# JTAG_Programmer.net
KiCad netlist of a schematic drawn in EAGLE
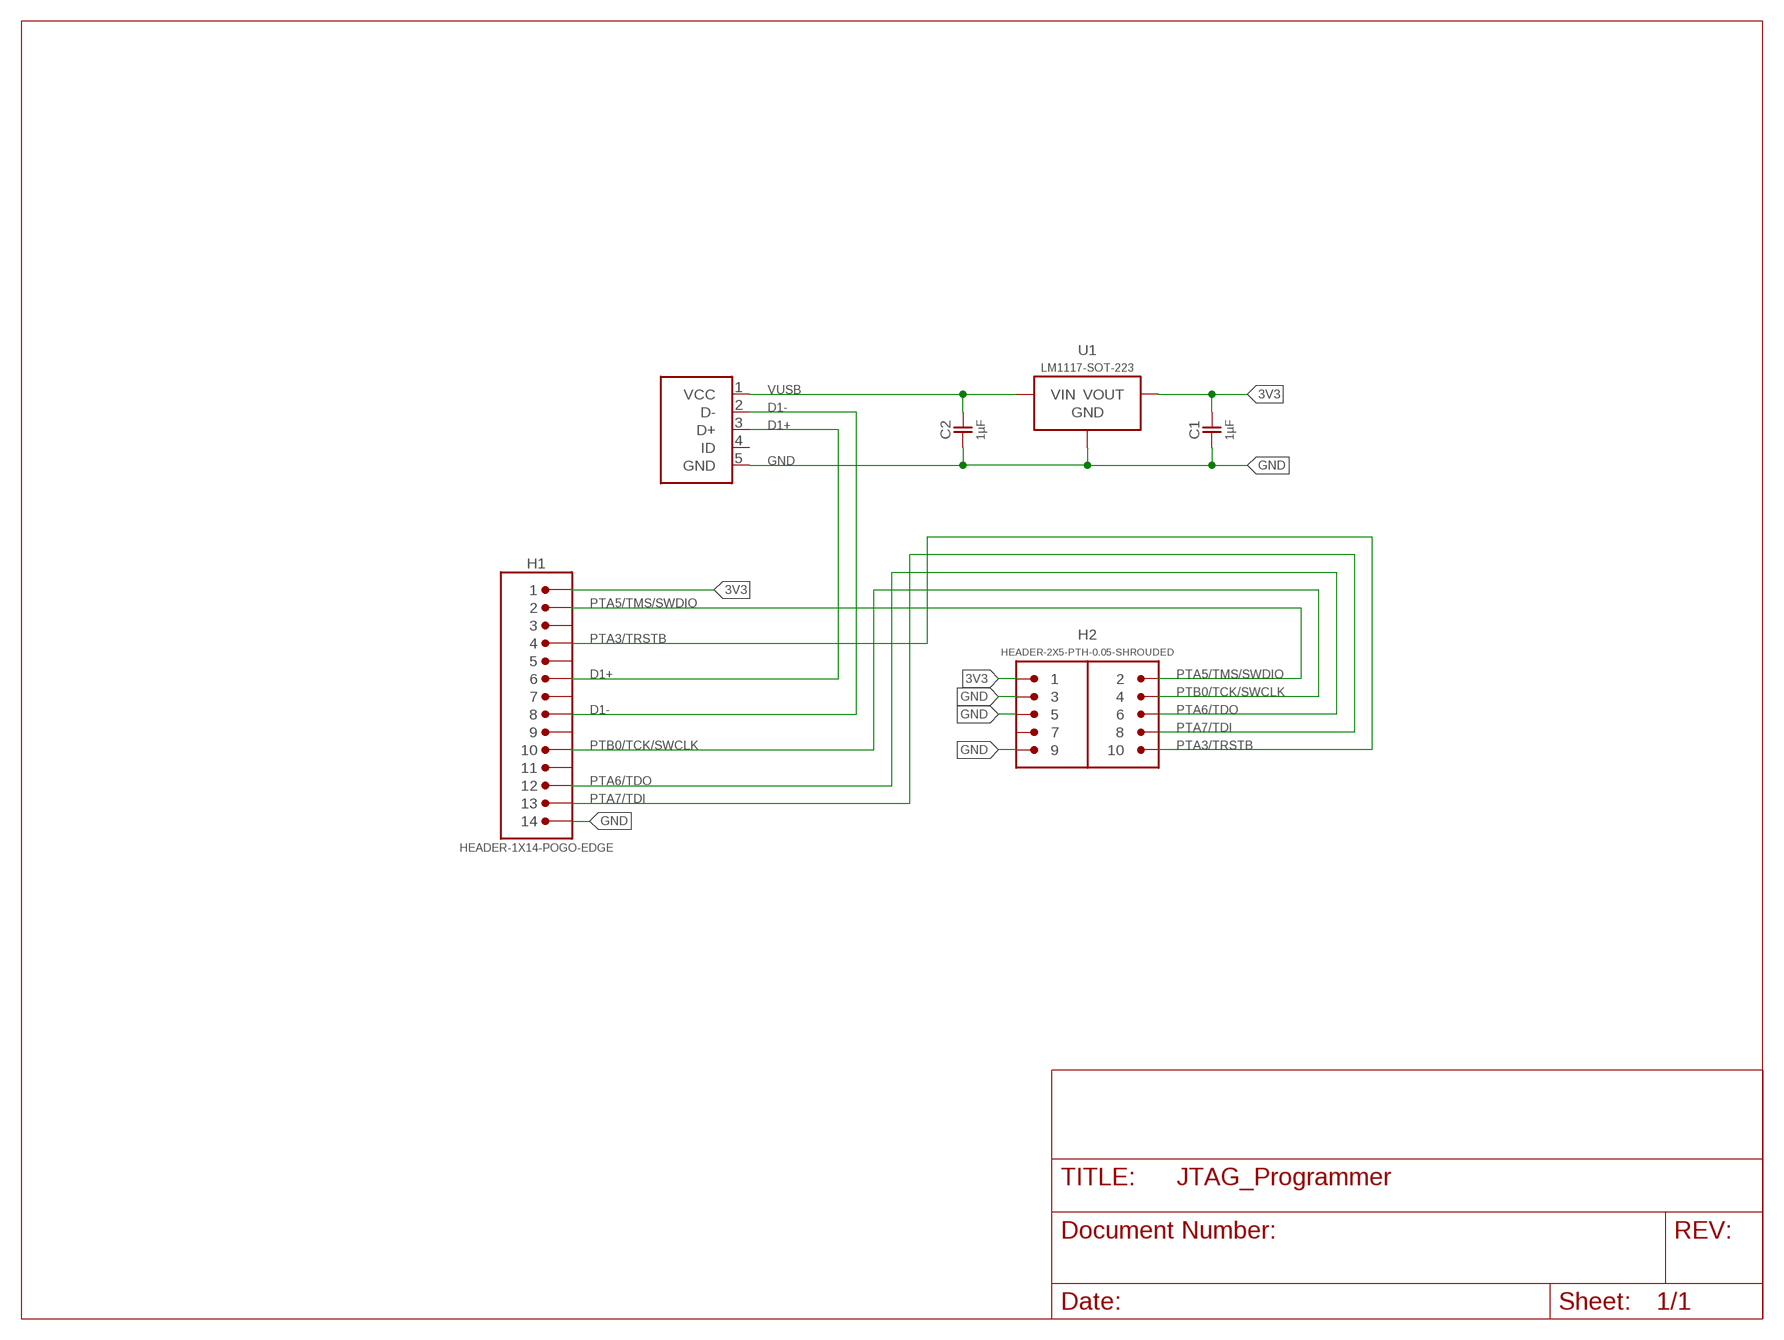
[diagram p0: schematic, sheet 1]

(export (version "E")
  (design (tool "Eeschema 10.0.6"))
  (components
    (comp (ref "C1")
      (value "1µF")
      (footprint "eagle-import:0805-NP")
      (libsource (lib "eagle-import") (part "CAP-NP-0805"))
    )
    (comp (ref "C2")
      (value "1µF")
      (footprint "eagle-import:0805-NP")
      (libsource (lib "eagle-import") (part "CAP-NP-0805"))
    )
    (comp (ref "H1")
      (value "HEADER-1X14-POGO-EDGE")
      (footprint "eagle-import:2X7-1.27MM-POGO-EDGE")
      (libsource (lib "eagle-import") (part "HEADER-1X14-POGO-EDGE"))
    )
    (comp (ref "H2")
      (value "HEADER-2X5-PTH-0.05-SHROUDED")
      (footprint "eagle-import:PTH-0.05-2X5-SHROUDED")
      (libsource (lib "eagle-import") (part "HEADER-2X5-PTH-0.05-SHROUDED"))
    )
    (comp (ref "J1")
      (value "USB-5-MICRO-B")
      (footprint "eagle-import:USB-MICRO-B")
      (libsource (lib "eagle-import") (part "USB-5-MICRO-B"))
    )
    (comp (ref "U1")
      (value "LM1117-SOT-223")
      (footprint "eagle-import:SOT-223")
      (libsource (lib "eagle-import") (part "LM1117-SOT-223"))
    )
  )
  (nets
    (net (code "1") (name "/D1+") (class "Default")
      (node (ref "H1") (pin "6") (pinfunction "6_6") (pintype "bidirectional"))
      (node (ref "J1") (pin "3") (pinfunction "D+_3") (pintype "bidirectional"))
    )
    (net (code "2") (name "/D1-") (class "Default")
      (node (ref "H1") (pin "8") (pinfunction "8_8") (pintype "bidirectional"))
      (node (ref "J1") (pin "2") (pinfunction "D-_2") (pintype "bidirectional"))
    )
    (net (code "3") (name "/PTA3{slash}TRSTB") (class "Default")
      (node (ref "H1") (pin "4") (pinfunction "4_4") (pintype "bidirectional"))
      (node (ref "H2") (pin "10") (pinfunction "10_10") (pintype "bidirectional"))
    )
    (net (code "4") (name "/PTA5{slash}TMS{slash}SWDIO") (class "Default")
      (node (ref "H1") (pin "2") (pinfunction "2_2") (pintype "bidirectional"))
      (node (ref "H2") (pin "2") (pinfunction "2_2") (pintype "bidirectional"))
    )
    (net (code "5") (name "/PTA6{slash}TDO") (class "Default")
      (node (ref "H1") (pin "12") (pinfunction "12_12") (pintype "bidirectional"))
      (node (ref "H2") (pin "6") (pinfunction "6_6") (pintype "bidirectional"))
    )
    (net (code "6") (name "/PTA7{slash}TDI") (class "Default")
      (node (ref "H1") (pin "13") (pinfunction "13_13") (pintype "bidirectional"))
      (node (ref "H2") (pin "8") (pinfunction "8_8") (pintype "bidirectional"))
    )
    (net (code "7") (name "/PTB0{slash}TCK{slash}SWCLK") (class "Default")
      (node (ref "H1") (pin "10") (pinfunction "10_10") (pintype "bidirectional"))
      (node (ref "H2") (pin "4") (pinfunction "4_4") (pintype "bidirectional"))
    )
    (net (code "8") (name "/VUSB") (class "Default")
      (node (ref "C2") (pin "2") (pinfunction "2_2") (pintype "bidirectional"))
      (node (ref "J1") (pin "1") (pinfunction "VCC_1") (pintype "bidirectional"))
      (node (ref "U1") (pin "3") (pinfunction "VIN_3") (pintype "input"))
    )
    (net (code "9") (name "3V3") (class "Default")
      (node (ref "C1") (pin "2") (pinfunction "2_2") (pintype "bidirectional"))
      (node (ref "H1") (pin "1") (pinfunction "1_1") (pintype "bidirectional"))
      (node (ref "H2") (pin "1") (pinfunction "1_1") (pintype "bidirectional"))
      (node (ref "U1") (pin "2") (pinfunction "VOUT_2") (pintype "output"))
      (node (ref "U1") (pin "4") (pinfunction "VOUT_4") (pintype "output"))
    )
    (net (code "10") (name "GND") (class "Default")
      (node (ref "C1") (pin "1") (pinfunction "1_1") (pintype "bidirectional"))
      (node (ref "C2") (pin "1") (pinfunction "1_1") (pintype "bidirectional"))
      (node (ref "H1") (pin "14") (pinfunction "14_14") (pintype "bidirectional"))
      (node (ref "H2") (pin "3") (pinfunction "3_3") (pintype "bidirectional"))
      (node (ref "H2") (pin "5") (pinfunction "5_5") (pintype "bidirectional"))
      (node (ref "H2") (pin "9") (pinfunction "9_9") (pintype "bidirectional"))
      (node (ref "J1") (pin "5") (pinfunction "GND_5") (pintype "bidirectional"))
      (node (ref "U1") (pin "1") (pinfunction "GND_1") (pintype "power_in"))
    )
    (net (code "11") (name "unconnected-(H1-Pad3)") (class "Default")
      (node (ref "H1") (pin "3") (pinfunction "3_3") (pintype "bidirectional"))
    )
    (net (code "12") (name "unconnected-(H1-Pad5)") (class "Default")
      (node (ref "H1") (pin "5") (pinfunction "5_5") (pintype "bidirectional"))
    )
    (net (code "13") (name "unconnected-(H1-Pad7)") (class "Default")
      (node (ref "H1") (pin "7") (pinfunction "7_7") (pintype "bidirectional"))
    )
    (net (code "14") (name "unconnected-(H1-Pad9)") (class "Default")
      (node (ref "H1") (pin "9") (pinfunction "9_9") (pintype "bidirectional"))
    )
    (net (code "15") (name "unconnected-(H1-Pad11)") (class "Default")
      (node (ref "H1") (pin "11") (pinfunction "11_11") (pintype "bidirectional"))
    )
    (net (code "16") (name "unconnected-(H2-Pad7)") (class "Default")
      (node (ref "H2") (pin "7") (pinfunction "7_7") (pintype "bidirectional"))
    )
    (net (code "17") (name "unconnected-(J1-ID-Pad4)") (class "Default")
      (node (ref "J1") (pin "4") (pinfunction "ID_4") (pintype "bidirectional"))
    )
  )
)
